# Pmaster-A9112-HOST_1.net
KiCad netlist of a schematic drawn in Altium Designer
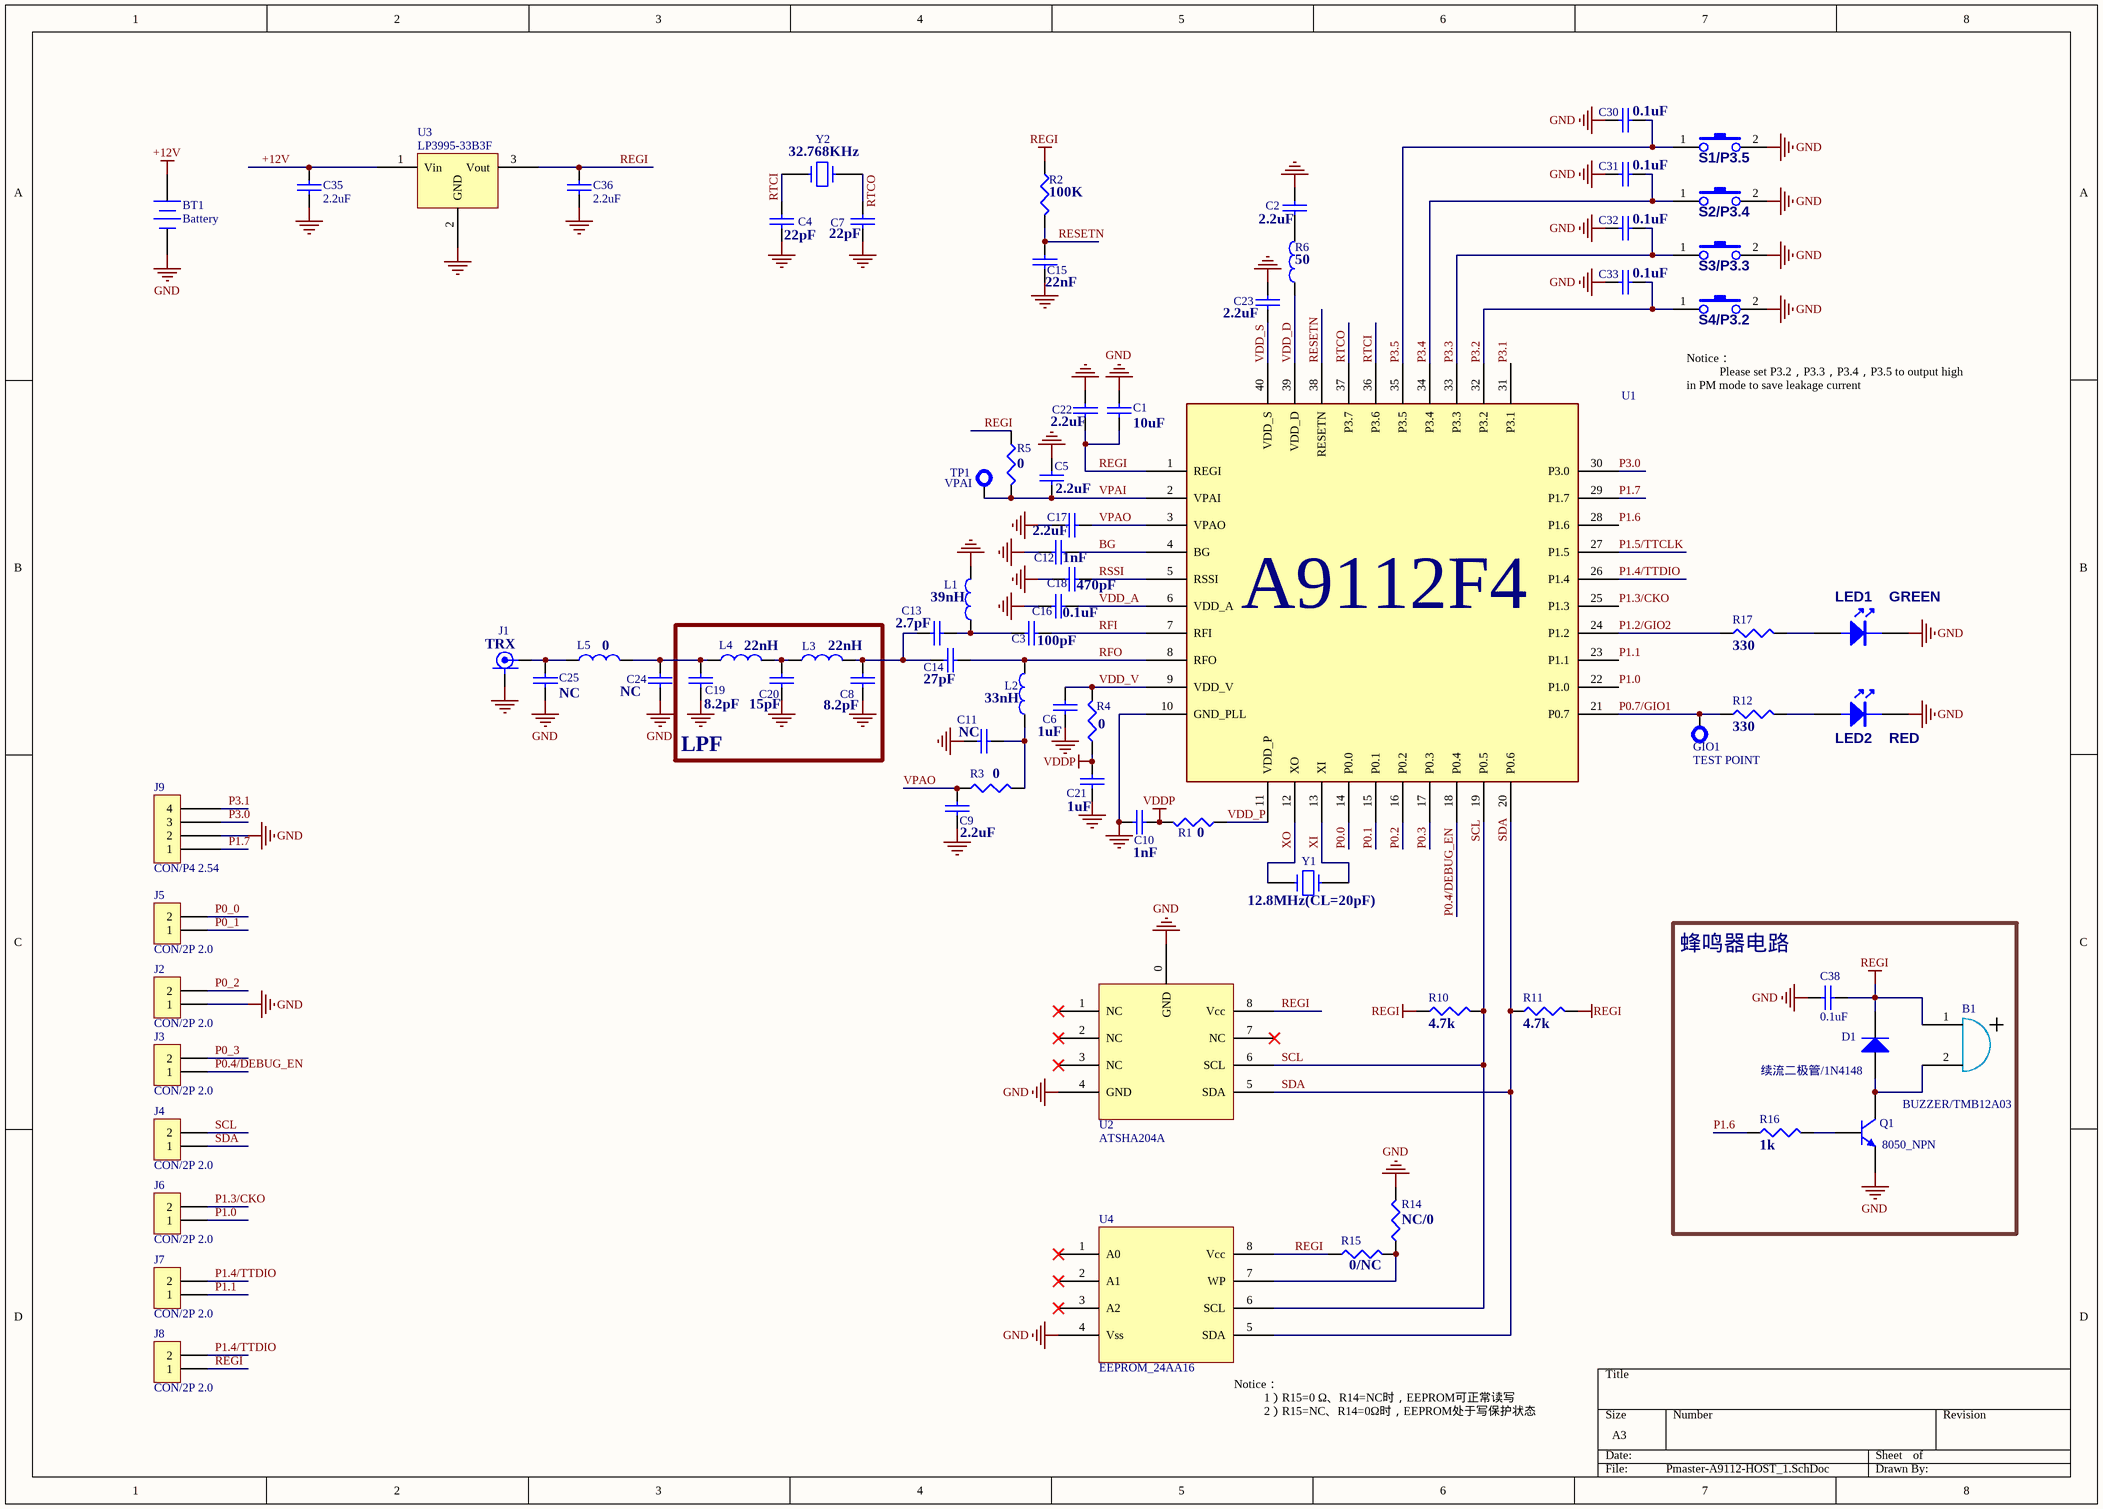
[diagram p0: Pmaster-A9112-HOST_1.SchDoc]

(export (version "E")
  (design (tool "Eeschema 10.0.6"))
  (components
    (comp (ref "B1")
      (value "BUZZER/TMB12A03")
      (footprint "BUZEER")
      (libsource (lib "my-amiccom") (part "BUZZER"))
    )
    (comp (ref "BT1")
      (value "Battery")
      (footprint "BAT-2")
      (description "Multicell Battery")
      (fields (field (name "PUBLISHER") "Altium Limited"))
      (libsource (lib "Miscellaneous Devices") (part "Battery"))
    )
    (comp (ref "C1") (value "10uF") (footprint "1206") (libsource (lib "*") (part "CAP")))
    (comp (ref "C2") (value "2.2uF") (footprint "0603") (libsource (lib "*") (part "CAP")))
    (comp (ref "C3") (value "100pF") (footprint "0402") (libsource (lib "*") (part "CAP")))
    (comp (ref "C4")
      (value "22pF")
      (footprint "0402")
      (description "Chip C")
      (libsource (lib "*") (part "C/0402"))
    )
    (comp (ref "C5") (value "2.2uF") (footprint "0603") (libsource (lib "*") (part "CAP")))
    (comp (ref "C6") (value "1uF") (footprint "0603") (libsource (lib "*") (part "CAP")))
    (comp (ref "C7")
      (value "22pF")
      (footprint "0402")
      (description "Chip C")
      (libsource (lib "*") (part "C/0402"))
    )
    (comp (ref "C8") (value "8.2pF") (footprint "0402") (libsource (lib "*") (part "CAP")))
    (comp (ref "C9")
      (value "2.2uF")
      (footprint "0603")
      (description "Chip C")
      (libsource (lib "*") (part "C/0603"))
    )
    (comp (ref "C10") (value "1nF") (footprint "0402") (libsource (lib "*") (part "CAP")))
    (comp (ref "C11")
      (value "NC")
      (footprint "0402")
      (description "Chip C")
      (libsource (lib "*") (part "C/0603"))
    )
    (comp (ref "C12") (value "1nF") (footprint "0402") (libsource (lib "*") (part "CAP")))
    (comp (ref "C13") (value "2.7pF") (footprint "0402") (libsource (lib "*") (part "CAP")))
    (comp (ref "C14") (value "27pF") (footprint "0402") (libsource (lib "*") (part "CAP")))
    (comp (ref "C15")
      (value "22nF")
      (footprint "0402")
      (description "Chip C")
      (libsource (lib "*") (part "C/1206"))
    )
    (comp (ref "C16") (value "0.1uF") (footprint "0603") (libsource (lib "*") (part "CAP")))
    (comp (ref "C17")
      (value "2.2uF")
      (footprint "0603")
      (description "Chip C")
      (libsource (lib "*") (part "C/0603"))
    )
    (comp (ref "C18") (value "470pF") (footprint "0402") (libsource (lib "*") (part "CAP")))
    (comp (ref "C19")
      (value "8.2pF")
      (footprint "0402")
      (description "Chip C")
      (libsource (lib "*") (part "C/0603"))
    )
    (comp (ref "C20")
      (value "15pF")
      (footprint "0402")
      (description "Chip C")
      (libsource (lib "*") (part "C/0603"))
    )
    (comp (ref "C21") (value "1uF") (footprint "0402") (libsource (lib "*") (part "CAP")))
    (comp (ref "C22") (value "2.2uF") (footprint "0603") (libsource (lib "*") (part "CAP")))
    (comp (ref "C23") (value "2.2uF") (footprint "0603") (libsource (lib "*") (part "CAP")))
    (comp (ref "C24") (value "NC") (footprint "0402") (libsource (lib "*") (part "CAP")))
    (comp (ref "C25") (value "NC") (footprint "0402") (libsource (lib "*") (part "CAP")))
    (comp (ref "C30") (value "0.1uF") (footprint "0603") (libsource (lib "*") (part "CAP")))
    (comp (ref "C31") (value "0.1uF") (footprint "0603") (libsource (lib "*") (part "CAP")))
    (comp (ref "C32") (value "0.1uF") (footprint "0603") (libsource (lib "*") (part "CAP")))
    (comp (ref "C33") (value "0.1uF") (footprint "0603") (libsource (lib "*") (part "CAP")))
    (comp (ref "C35") (value "2.2uF") (footprint "0603") (libsource (lib "") (part "CAP_1")))
    (comp (ref "C36")
      (value "2.2uF")
      (footprint "0603")
      (description "Chip C")
      (libsource (lib "*") (part "C/0603"))
    )
    (comp (ref "C38")
      (value "0.1uF")
      (footprint "A0402")
      (description "Chip C")
      (libsource (lib "*") (part "C/0603"))
    )
    (comp (ref "D1")
      (value "续流二极管/1N4148")
      (footprint "0805")
      (description "Default Diode")
      (fields (field (name "PUBLISHER") "Altium Limited"))
      (libsource (lib "Miscellaneous Devices") (part "Diode"))
    )
    (comp (ref "GIO1") (value "TEST POINT") (footprint "DIPOLE") (libsource (lib "my-amiccom") (part "TP")))
    (comp (ref "J1") (value "TRX") (footprint "SMA CONNECTOR") (libsource (lib "*") (part "SMA CONNECTOR")))
    (comp (ref "J2")
      (value "CON/2P 2.0")
      (footprint "HDR2_2.0")
      (description "Hole 36mil")
      (libsource (lib "my-amiccom") (part "CON/2P 2.0"))
    )
    (comp (ref "J3")
      (value "CON/2P 2.0")
      (footprint "HDR2_2.0")
      (description "Hole 36mil")
      (libsource (lib "my-amiccom") (part "CON/2P 2.0"))
    )
    (comp (ref "J4")
      (value "CON/2P 2.0")
      (footprint "HDR2_2.0")
      (description "Hole 36mil")
      (libsource (lib "my-amiccom") (part "CON/2P 2.0"))
    )
    (comp (ref "J5")
      (value "CON/2P 2.0")
      (footprint "HDR2_2.0")
      (description "Hole 36mil")
      (libsource (lib "my-amiccom") (part "CON/2P 2.0"))
    )
    (comp (ref "J6")
      (value "CON/2P 2.0")
      (footprint "HDR2_2.0")
      (description "Hole 36mil")
      (libsource (lib "my-amiccom") (part "CON/2P 2.0"))
    )
    (comp (ref "J7")
      (value "CON/2P 2.0")
      (footprint "HDR2_2.0")
      (description "Hole 36mil")
      (libsource (lib "my-amiccom") (part "CON/2P 2.0"))
    )
    (comp (ref "J8")
      (value "CON/2P 2.0")
      (footprint "HDR2_2.0")
      (description "Hole 36mil")
      (libsource (lib "my-amiccom") (part "CON/2P 2.0"))
    )
    (comp (ref "J9") (value "CON/P4 2.54") (libsource (lib "my-amiccom") (part "CON/P4 2.54")))
    (comp (ref "L1")
      (value "39nH")
      (footprint "0402")
      (description "Chip L")
      (libsource (lib "*") (part "L/0402"))
    )
    (comp (ref "L2")
      (value "33nH")
      (footprint "0402")
      (description "Chip L")
      (libsource (lib "*") (part "L/0402"))
    )
    (comp (ref "L3") (value "22nH") (footprint "0402") (libsource (lib "") (part "L/0603_1")))
    (comp (ref "L4") (value "22nH") (footprint "0402") (libsource (lib "") (part "L/0603_1")))
    (comp (ref "L5") (value "0") (footprint "0402") (libsource (lib "") (part "L/0603_1")))
    (comp (ref "LED1") (value "GREEN") (footprint "0603") (libsource (lib "my-amiccom") (part "LED")))
    (comp (ref "LED2") (value "RED") (footprint "0603") (libsource (lib "my-amiccom") (part "LED")))
    (comp (ref "Q1")
      (value "8050_NPN")
      (footprint "SOT-23_N")
      (description "NPN Bipolar Transistor")
      (fields (field (name "PUBLISHER") "Altium Limited"))
      (libsource (lib "Miscellaneous Devices") (part "NPN"))
    )
    (comp (ref "R1") (value "0") (footprint "0402") (libsource (lib "*") (part "RES1")))
    (comp (ref "R2")
      (value "100K")
      (footprint "0402")
      (description "Chip R")
      (libsource (lib "*") (part "R/0402"))
    )
    (comp (ref "R3")
      (value "0")
      (footprint "0402")
      (description "Chip  R")
      (libsource (lib "*") (part "R/0603"))
    )
    (comp (ref "R4")
      (value "0")
      (footprint "0402")
      (description "Chip  R")
      (libsource (lib "*") (part "R/0603"))
    )
    (comp (ref "R5") (value "0") (footprint "0402") (libsource (lib "*") (part "RES1")))
    (comp (ref "R6") (value "50") (footprint "0402") (libsource (lib "*") (part "L/0603")))
    (comp (ref "R10") (value "4.7k") (footprint "0402") (libsource (lib "*") (part "RES1")))
    (comp (ref "R11") (value "4.7k") (footprint "0402") (libsource (lib "*") (part "RES1")))
    (comp (ref "R12") (value "330") (footprint "0402") (libsource (lib "*") (part "RES1")))
    (comp (ref "R14") (value "NC/0") (footprint "0402") (libsource (lib "*") (part "RES1")))
    (comp (ref "R15") (value "0/NC") (footprint "0402") (libsource (lib "*") (part "RES1")))
    (comp (ref "R16") (value "1k") (footprint "0402") (libsource (lib "*") (part "RES1")))
    (comp (ref "R17") (value "330") (footprint "0402") (libsource (lib "*") (part "RES1")))
    (comp (ref "S1/P3.5")
      (value "SW-P~{B}2P")
      (footprint "SW2P")
      (libsource (lib "my-amiccom") (part "SW-PB{backslash}2P"))
    )
    (comp (ref "S2/P3.4")
      (value "SW-P~{B}2P")
      (footprint "SW2P")
      (libsource (lib "my-amiccom") (part "SW-PB{backslash}2P"))
    )
    (comp (ref "S3/P3.3")
      (value "SW-P~{B}2P")
      (footprint "SW2P")
      (libsource (lib "my-amiccom") (part "SW-PB{backslash}2P"))
    )
    (comp (ref "S4/P3.2")
      (value "SW-P~{B}2P")
      (footprint "SW2P")
      (libsource (lib "my-amiccom") (part "SW-PB{backslash}2P"))
    )
    (comp (ref "TP1") (value "VPAI") (footprint "HDR1_2.54") (libsource (lib "test LIB") (part "TP")))
    (comp (ref "U1")
      (value "A9112F4")
      (footprint "QFN 5*5 40L")
      (libsource (lib "AMICCOM-S") (part "A9112F4"))
    )
    (comp (ref "U2")
      (value "ATSHA204A")
      (footprint "UDFN_8P")
      (libsource (lib "my-amiccom") (part "ATSHA204A"))
    )
    (comp (ref "U3")
      (value "LP3995-33B3F")
      (footprint "SOT-223")
      (description "GMT 3.3V REGULTOR")
      (libsource (lib "*") (part "REG{backslash}G903{backslash}3.3V{backslash}SOT-223"))
    )
    (comp (ref "U4")
      (value "EEPROM_24AA16")
      (footprint "MSOP-MS8_N")
      (libsource (lib "my-amiccom") (part "EEPROM_24AA16"))
    )
    (comp (ref "Y1")
      (value "12.8MHz(CL=20pF)")
      (footprint "XTAL1")
      (description "Crystal")
      (libsource (lib "*") (part "CRYSTAL"))
    )
    (comp (ref "Y2")
      (value "32.768KHz")
      (footprint "xtal-3215")
      (description "Crystal")
      (libsource (lib "*") (part "CRYSTAL"))
    )
  )
  (nets
    (net (code "1") (name "+12V") (class "Default")
      (node (ref "BT1") (pin "1") (pinfunction "+_1") (pintype "passive"))
      (node (ref "C35") (pin "2") (pinfunction "2_2") (pintype "passive"))
      (node (ref "U3") (pin "1") (pinfunction "Vin_1") (pintype "passive"))
    )
    (net (code "2") (name "/BG") (class "Default")
      (node (ref "C12") (pin "1") (pinfunction "1_1") (pintype "passive"))
      (node (ref "U1") (pin "4") (pinfunction "BG_4") (pintype "passive"))
    )
    (net (code "3") (name "/P0.0") (class "Default")
      (node (ref "U1") (pin "14") (pinfunction "P0.0_14") (pintype "passive"))
    )
    (net (code "4") (name "/P0.1") (class "Default")
      (node (ref "U1") (pin "15") (pinfunction "P0.1_15") (pintype "passive"))
    )
    (net (code "5") (name "/P0.2") (class "Default")
      (node (ref "U1") (pin "16") (pinfunction "P0.2_16") (pintype "passive"))
    )
    (net (code "6") (name "/P0.3") (class "Default")
      (node (ref "U1") (pin "17") (pinfunction "P0.3_17") (pintype "passive"))
    )
    (net (code "7") (name "/P0.4{slash}DEBUG_EN") (class "Default")
      (node (ref "J3") (pin "1") (pinfunction "1_1") (pintype "passive"))
      (node (ref "U1") (pin "18") (pinfunction "P0.4_18") (pintype "passive"))
    )
    (net (code "8") (name "/P0.7{slash}GIO1") (class "Default")
      (node (ref "GIO1") (pin "1") (pinfunction "1_1") (pintype "passive"))
      (node (ref "R12") (pin "1") (pinfunction "1_1") (pintype "passive"))
      (node (ref "U1") (pin "21") (pinfunction "P0.7_21") (pintype "passive"))
    )
    (net (code "9") (name "/P0_0") (class "Default")
      (node (ref "J5") (pin "2") (pinfunction "2_2") (pintype "passive"))
    )
    (net (code "10") (name "/P0_1") (class "Default")
      (node (ref "J5") (pin "1") (pinfunction "1_1") (pintype "passive"))
    )
    (net (code "11") (name "/P0_2") (class "Default")
      (node (ref "J2") (pin "2") (pinfunction "2_2") (pintype "passive"))
    )
    (net (code "12") (name "/P0_3") (class "Default")
      (node (ref "J3") (pin "2") (pinfunction "2_2") (pintype "passive"))
    )
    (net (code "13") (name "/P1.0") (class "Default")
      (node (ref "J6") (pin "1") (pinfunction "1_1") (pintype "passive"))
      (node (ref "U1") (pin "22") (pinfunction "P1.0_22") (pintype "passive"))
    )
    (net (code "14") (name "/P1.1") (class "Default")
      (node (ref "J7") (pin "1") (pinfunction "1_1") (pintype "passive"))
      (node (ref "U1") (pin "23") (pinfunction "P1.1_23") (pintype "passive"))
    )
    (net (code "15") (name "/P1.2{slash}GIO2") (class "Default")
      (node (ref "R17") (pin "1") (pinfunction "1_1") (pintype "passive"))
      (node (ref "U1") (pin "24") (pinfunction "P1.2_24") (pintype "passive"))
    )
    (net (code "16") (name "/P1.3{slash}CKO") (class "Default")
      (node (ref "J6") (pin "2") (pinfunction "2_2") (pintype "passive"))
      (node (ref "U1") (pin "25") (pinfunction "P1.3_25") (pintype "passive"))
    )
    (net (code "17") (name "/P1.4{slash}TTDIO") (class "Default")
      (node (ref "J7") (pin "2") (pinfunction "2_2") (pintype "passive"))
      (node (ref "J8") (pin "2") (pinfunction "2_2") (pintype "passive"))
      (node (ref "U1") (pin "26") (pinfunction "P1.4_26") (pintype "passive"))
    )
    (net (code "18") (name "/P1.5{slash}TTCLK") (class "Default")
      (node (ref "U1") (pin "27") (pinfunction "P1.5_27") (pintype "passive"))
    )
    (net (code "19") (name "/P1.6") (class "Default")
      (node (ref "R16") (pin "1") (pinfunction "1_1") (pintype "passive"))
      (node (ref "U1") (pin "28") (pinfunction "P1.6_28") (pintype "passive"))
    )
    (net (code "20") (name "/P1.7") (class "Default")
      (node (ref "J9") (pin "1") (pinfunction "1_1") (pintype "power_in"))
      (node (ref "U1") (pin "29") (pinfunction "P1.7_29") (pintype "passive"))
    )
    (net (code "21") (name "/P3.0") (class "Default")
      (node (ref "J9") (pin "3") (pinfunction "3_3") (pintype "power_in"))
      (node (ref "U1") (pin "30") (pinfunction "P3.0_30") (pintype "passive"))
    )
    (net (code "22") (name "/P3.1") (class "Default")
      (node (ref "J9") (pin "4") (pinfunction "4_4") (pintype "power_in"))
      (node (ref "U1") (pin "31") (pinfunction "P3.1_31") (pintype "passive"))
    )
    (net (code "23") (name "/P3.2") (class "Default")
      (node (ref "C33") (pin "2") (pinfunction "2_2") (pintype "passive"))
      (node (ref "S4/P3.2") (pin "1") (pinfunction "1_1") (pintype "passive"))
      (node (ref "U1") (pin "32") (pinfunction "P3.2_32") (pintype "passive"))
    )
    (net (code "24") (name "/P3.3") (class "Default")
      (node (ref "C32") (pin "2") (pinfunction "2_2") (pintype "passive"))
      (node (ref "S3/P3.3") (pin "1") (pinfunction "1_1") (pintype "passive"))
      (node (ref "U1") (pin "33") (pinfunction "P3.3_33") (pintype "passive"))
    )
    (net (code "25") (name "/P3.4") (class "Default")
      (node (ref "C31") (pin "2") (pinfunction "2_2") (pintype "passive"))
      (node (ref "S2/P3.4") (pin "1") (pinfunction "1_1") (pintype "passive"))
      (node (ref "U1") (pin "34") (pinfunction "P3.4_34") (pintype "passive"))
    )
    (net (code "26") (name "/P3.5") (class "Default")
      (node (ref "C30") (pin "2") (pinfunction "2_2") (pintype "passive"))
      (node (ref "S1/P3.5") (pin "1") (pinfunction "1_1") (pintype "passive"))
      (node (ref "U1") (pin "35") (pinfunction "P3.5_35") (pintype "passive"))
    )
    (net (code "27") (name "/RESETN") (class "Default")
      (node (ref "C15") (pin "1") (pinfunction "1_1") (pintype "passive"))
      (node (ref "R2") (pin "2") (pinfunction "2_2") (pintype "passive"))
      (node (ref "U1") (pin "38") (pinfunction "RESETN_38") (pintype "passive"))
    )
    (net (code "28") (name "/RFI") (class "Default")
      (node (ref "C3") (pin "1") (pinfunction "1_1") (pintype "passive"))
      (node (ref "U1") (pin "7") (pinfunction "RFI_7") (pintype "passive"))
    )
    (net (code "29") (name "/RFO") (class "Default")
      (node (ref "C14") (pin "1") (pinfunction "1_1") (pintype "passive"))
      (node (ref "L2") (pin "2") (pinfunction "2_2") (pintype "passive"))
      (node (ref "U1") (pin "8") (pinfunction "RFO_8") (pintype "passive"))
    )
    (net (code "30") (name "/RSSI") (class "Default")
      (node (ref "C18") (pin "2") (pinfunction "2_2") (pintype "passive"))
      (node (ref "U1") (pin "5") (pinfunction "RSSI_5") (pintype "passive"))
    )
    (net (code "31") (name "/RTCI") (class "Default")
      (node (ref "C4") (pin "1") (pinfunction "1_1") (pintype "passive"))
      (node (ref "U1") (pin "36") (pinfunction "P3.6_36") (pintype "passive"))
      (node (ref "Y2") (pin "1") (pinfunction "1_1") (pintype "passive"))
    )
    (net (code "32") (name "/RTCO") (class "Default")
      (node (ref "C7") (pin "1") (pinfunction "1_1") (pintype "passive"))
      (node (ref "U1") (pin "37") (pinfunction "P3.7_37") (pintype "passive"))
      (node (ref "Y2") (pin "2") (pinfunction "2_2") (pintype "passive"))
    )
    (net (code "33") (name "/SCL") (class "Default")
      (node (ref "J4") (pin "2") (pinfunction "2_2") (pintype "passive"))
      (node (ref "R10") (pin "2") (pinfunction "2_2") (pintype "passive"))
      (node (ref "U1") (pin "19") (pinfunction "P0.5_19") (pintype "passive"))
      (node (ref "U2") (pin "6") (pinfunction "SCL_6") (pintype "passive"))
      (node (ref "U4") (pin "6") (pinfunction "SCL_6") (pintype "passive"))
    )
    (net (code "34") (name "/SDA") (class "Default")
      (node (ref "J4") (pin "1") (pinfunction "1_1") (pintype "passive"))
      (node (ref "R11") (pin "1") (pinfunction "1_1") (pintype "passive"))
      (node (ref "U1") (pin "20") (pinfunction "P0.6_20") (pintype "passive"))
      (node (ref "U2") (pin "5") (pinfunction "SDA_5") (pintype "passive"))
      (node (ref "U4") (pin "5") (pinfunction "SDA_5") (pintype "passive"))
    )
    (net (code "35") (name "/VDD_A") (class "Default")
      (node (ref "C16") (pin "2") (pinfunction "2_2") (pintype "passive"))
      (node (ref "U1") (pin "6") (pinfunction "VDD_A_6") (pintype "passive"))
    )
    (net (code "36") (name "/VDD_D") (class "Default")
      (node (ref "R6") (pin "1") (pinfunction "1_1") (pintype "passive"))
      (node (ref "U1") (pin "39") (pinfunction "VDD_D_39") (pintype "passive"))
    )
    (net (code "37") (name "/VDD_P") (class "Default")
      (node (ref "R1") (pin "1") (pinfunction "1_1") (pintype "passive"))
      (node (ref "U1") (pin "11") (pinfunction "VDD_P_11") (pintype "passive"))
    )
    (net (code "39") (name "/VDD_S") (class "Default")
      (node (ref "C23") (pin "2") (pinfunction "2_2") (pintype "passive"))
      (node (ref "U1") (pin "40") (pinfunction "VDD_S_40") (pintype "passive"))
    )
    (net (code "40") (name "/VDD_V") (class "Default")
      (node (ref "C6") (pin "1") (pinfunction "1_1") (pintype "passive"))
      (node (ref "R4") (pin "2") (pinfunction "2_2") (pintype "passive"))
      (node (ref "U1") (pin "9") (pinfunction "VDD_V_9") (pintype "passive"))
    )
    (net (code "41") (name "/VPAI") (class "Default")
      (node (ref "C5") (pin "1") (pinfunction "1_1") (pintype "passive"))
      (node (ref "R5") (pin "2") (pinfunction "2_2") (pintype "passive"))
      (node (ref "TP1") (pin "1") (pinfunction "1_1") (pintype "passive"))
      (node (ref "U1") (pin "2") (pinfunction "VPAI_2") (pintype "passive"))
    )
    (net (code "42") (name "/VPAO") (class "Default")
      (node (ref "C17") (pin "1") (pinfunction "1_1") (pintype "passive"))
      (node (ref "C9") (pin "1") (pinfunction "1_1") (pintype "passive"))
      (node (ref "R3") (pin "1") (pinfunction "1_1") (pintype "passive"))
      (node (ref "U1") (pin "3") (pinfunction "VPAO_3") (pintype "passive"))
    )
    (net (code "43") (name "/XI") (class "Default")
      (node (ref "U1") (pin "13") (pinfunction "XI_13") (pintype "passive"))
      (node (ref "Y1") (pin "1") (pinfunction "1_1") (pintype "passive"))
    )
    (net (code "44") (name "/XO") (class "Default")
      (node (ref "U1") (pin "12") (pinfunction "XO_12") (pintype "passive"))
      (node (ref "Y1") (pin "2") (pinfunction "2_2") (pintype "passive"))
    )
    (net (code "45") (name "GND") (class "Default")
      (node (ref "BT1") (pin "2") (pinfunction "-_2") (pintype "passive"))
      (node (ref "C1") (pin "2") (pinfunction "2_2") (pintype "passive"))
      (node (ref "C10") (pin "1") (pinfunction "1_1") (pintype "passive"))
      (node (ref "C11") (pin "1") (pinfunction "1_1") (pintype "passive"))
      (node (ref "C12") (pin "2") (pinfunction "2_2") (pintype "passive"))
      (node (ref "C15") (pin "2") (pinfunction "2_2") (pintype "passive"))
      (node (ref "C16") (pin "1") (pinfunction "1_1") (pintype "passive"))
      (node (ref "C17") (pin "2") (pinfunction "2_2") (pintype "passive"))
      (node (ref "C18") (pin "1") (pinfunction "1_1") (pintype "passive"))
      (node (ref "C19") (pin "2") (pinfunction "2_2") (pintype "passive"))
      (node (ref "C2") (pin "1") (pinfunction "1_1") (pintype "passive"))
      (node (ref "C20") (pin "2") (pinfunction "2_2") (pintype "passive"))
      (node (ref "C21") (pin "1") (pinfunction "1_1") (pintype "passive"))
      (node (ref "C22") (pin "1") (pinfunction "1_1") (pintype "passive"))
      (node (ref "C23") (pin "1") (pinfunction "1_1") (pintype "passive"))
      (node (ref "C24") (pin "1") (pinfunction "1_1") (pintype "passive"))
      (node (ref "C25") (pin "1") (pinfunction "1_1") (pintype "passive"))
      (node (ref "C30") (pin "1") (pinfunction "1_1") (pintype "passive"))
      (node (ref "C31") (pin "1") (pinfunction "1_1") (pintype "passive"))
      (node (ref "C32") (pin "1") (pinfunction "1_1") (pintype "passive"))
      (node (ref "C33") (pin "1") (pinfunction "1_1") (pintype "passive"))
      (node (ref "C35") (pin "1") (pinfunction "1_1") (pintype "passive"))
      (node (ref "C36") (pin "2") (pinfunction "2_2") (pintype "passive"))
      (node (ref "C38") (pin "1") (pinfunction "1_1") (pintype "passive"))
      (node (ref "C4") (pin "2") (pinfunction "2_2") (pintype "passive"))
      (node (ref "C5") (pin "2") (pinfunction "2_2") (pintype "passive"))
      (node (ref "C7") (pin "2") (pinfunction "2_2") (pintype "passive"))
      (node (ref "C8") (pin "1") (pinfunction "1_1") (pintype "passive"))
      (node (ref "C9") (pin "2") (pinfunction "2_2") (pintype "passive"))
      (node (ref "J1") (pin "0") (pinfunction "SHIELD_0") (pintype "passive"))
      (node (ref "J2") (pin "1") (pinfunction "1_1") (pintype "passive"))
      (node (ref "J9") (pin "2") (pinfunction "2_2") (pintype "power_in"))
      (node (ref "L1") (pin "2") (pinfunction "2_2") (pintype "passive"))
      (node (ref "LED1") (pin "2") (pinfunction "K_2") (pintype "passive"))
      (node (ref "LED2") (pin "2") (pinfunction "K_2") (pintype "passive"))
      (node (ref "Q1") (pin "3") (pinfunction "E_3") (pintype "passive"))
      (node (ref "R14") (pin "2") (pinfunction "2_2") (pintype "passive"))
      (node (ref "S1/P3.5") (pin "2") (pinfunction "2_2") (pintype "passive"))
      (node (ref "S2/P3.4") (pin "2") (pinfunction "2_2") (pintype "passive"))
      (node (ref "S3/P3.3") (pin "2") (pinfunction "2_2") (pintype "passive"))
      (node (ref "S4/P3.2") (pin "2") (pinfunction "2_2") (pintype "passive"))
      (node (ref "U1") (pin "10") (pinfunction "GND_PLL_10") (pintype "passive"))
      (node (ref "U2") (pin "0") (pinfunction "GND_0") (pintype "passive"))
      (node (ref "U2") (pin "4") (pinfunction "GND_4") (pintype "passive"))
      (node (ref "U3") (pin "2") (pinfunction "GND_2") (pintype "passive"))
      (node (ref "U4") (pin "4") (pinfunction "Vss_4") (pintype "passive"))
    )
    (net (code "46") (name "Net-(C2-Pad2)") (class "Default")
      (node (ref "C2") (pin "2") (pinfunction "2_2") (pintype "passive"))
      (node (ref "R6") (pin "2") (pinfunction "2_2") (pintype "passive"))
    )
    (net (code "47") (name "Net-(C11-Pad2)") (class "Default")
      (node (ref "C11") (pin "2") (pinfunction "2_2") (pintype "passive"))
      (node (ref "L2") (pin "1") (pinfunction "1_1") (pintype "passive"))
      (node (ref "R3") (pin "2") (pinfunction "2_2") (pintype "passive"))
    )
    (net (code "48") (name "Net-(C13-Pad1)") (class "Default")
      (node (ref "C13") (pin "1") (pinfunction "1_1") (pintype "passive"))
      (node (ref "C3") (pin "2") (pinfunction "2_2") (pintype "passive"))
      (node (ref "L1") (pin "1") (pinfunction "1_1") (pintype "passive"))
    )
    (net (code "49") (name "Net-(C13-Pad2)") (class "Default")
      (node (ref "C13") (pin "2") (pinfunction "2_2") (pintype "passive"))
      (node (ref "C14") (pin "2") (pinfunction "2_2") (pintype "passive"))
      (node (ref "C8") (pin "2") (pinfunction "2_2") (pintype "passive"))
      (node (ref "L3") (pin "2") (pinfunction "2_2") (pintype "passive"))
    )
    (net (code "50") (name "Net-(C19-Pad1)") (class "Default")
      (node (ref "C19") (pin "1") (pinfunction "1_1") (pintype "passive"))
      (node (ref "C24") (pin "2") (pinfunction "2_2") (pintype "passive"))
      (node (ref "L4") (pin "1") (pinfunction "1_1") (pintype "passive"))
      (node (ref "L5") (pin "2") (pinfunction "2_2") (pintype "passive"))
    )
    (net (code "51") (name "Net-(C20-Pad1)") (class "Default")
      (node (ref "C20") (pin "1") (pinfunction "1_1") (pintype "passive"))
      (node (ref "L3") (pin "1") (pinfunction "1_1") (pintype "passive"))
      (node (ref "L4") (pin "2") (pinfunction "2_2") (pintype "passive"))
    )
    (net (code "52") (name "Net-(D1-A)") (class "Default")
      (node (ref "B1") (pin "2") (pintype "passive"))
      (node (ref "D1") (pin "1") (pinfunction "A_1") (pintype "passive"))
      (node (ref "Q1") (pin "1") (pinfunction "C_1") (pintype "passive"))
    )
    (net (code "53") (name "Net-(J1-CENTER_1)") (class "Default")
      (node (ref "C25") (pin "2") (pinfunction "2_2") (pintype "passive"))
      (node (ref "J1") (pin "1") (pinfunction "CENTER_1_1") (pintype "passive"))
      (node (ref "L5") (pin "1") (pinfunction "1_1") (pintype "passive"))
    )
    (net (code "54") (name "Net-(LED1-A)") (class "Default")
      (node (ref "LED1") (pin "1") (pinfunction "A_1") (pintype "passive"))
      (node (ref "R17") (pin "2") (pinfunction "2_2") (pintype "passive"))
    )
    (net (code "55") (name "Net-(LED2-A)") (class "Default")
      (node (ref "LED2") (pin "1") (pinfunction "A_1") (pintype "passive"))
      (node (ref "R12") (pin "2") (pinfunction "2_2") (pintype "passive"))
    )
    (net (code "56") (name "Net-(Q1-B)") (class "Default")
      (node (ref "Q1") (pin "2") (pinfunction "B_2") (pintype "passive"))
      (node (ref "R16") (pin "2") (pinfunction "2_2") (pintype "passive"))
    )
    (net (code "57") (name "Net-(U4-WP)") (class "Default")
      (node (ref "R14") (pin "1") (pinfunction "1_1") (pintype "passive"))
      (node (ref "R15") (pin "2") (pinfunction "2_2") (pintype "passive"))
      (node (ref "U4") (pin "7") (pinfunction "WP_7") (pintype "passive"))
    )
    (net (code "58") (name "REGI") (class "Default")
      (node (ref "B1") (pin "1") (pintype "passive"))
      (node (ref "C1") (pin "1") (pinfunction "1_1") (pintype "passive"))
      (node (ref "C22") (pin "2") (pinfunction "2_2") (pintype "passive"))
      (node (ref "C36") (pin "1") (pinfunction "1_1") (pintype "passive"))
      (node (ref "C38") (pin "2") (pinfunction "2_2") (pintype "passive"))
      (node (ref "D1") (pin "2") (pinfunction "K_2") (pintype "passive"))
      (node (ref "J8") (pin "1") (pinfunction "1_1") (pintype "passive"))
      (node (ref "R10") (pin "1") (pinfunction "1_1") (pintype "passive"))
      (node (ref "R11") (pin "2") (pinfunction "2_2") (pintype "passive"))
      (node (ref "R15") (pin "1") (pinfunction "1_1") (pintype "passive"))
      (node (ref "R2") (pin "1") (pinfunction "1_1") (pintype "passive"))
      (node (ref "R5") (pin "1") (pinfunction "1_1") (pintype "passive"))
      (node (ref "U1") (pin "1") (pinfunction "REGI_1") (pintype "passive"))
      (node (ref "U2") (pin "8") (pinfunction "Vcc_8") (pintype "passive"))
      (node (ref "U3") (pin "3") (pinfunction "Vout_3") (pintype "passive"))
      (node (ref "U4") (pin "8") (pinfunction "Vcc_8") (pintype "passive"))
    )
    (net (code "59") (name "VCO_GND") (class "Default")
      (node (ref "C6") (pin "2") (pinfunction "2_2") (pintype "passive"))
    )
    (net (code "60") (name "VDDP") (class "Default")
      (node (ref "C10") (pin "2") (pinfunction "2_2") (pintype "passive"))
      (node (ref "C21") (pin "2") (pinfunction "2_2") (pintype "passive"))
      (node (ref "R1") (pin "2") (pinfunction "2_2") (pintype "passive"))
      (node (ref "R4") (pin "1") (pinfunction "1_1") (pintype "passive"))
    )
    (net (code "61") (name "unconnected-(U2-NC-Pad1)") (class "Default")
      (node (ref "U2") (pin "1") (pinfunction "NC_1") (pintype "passive+no_connect"))
    )
    (net (code "62") (name "unconnected-(U2-NC-Pad2)") (class "Default")
      (node (ref "U2") (pin "2") (pinfunction "NC_2") (pintype "passive+no_connect"))
    )
    (net (code "63") (name "unconnected-(U2-NC-Pad3)") (class "Default")
      (node (ref "U2") (pin "3") (pinfunction "NC_3") (pintype "passive+no_connect"))
    )
    (net (code "64") (name "unconnected-(U2-NC-Pad7)") (class "Default")
      (node (ref "U2") (pin "7") (pinfunction "NC_7") (pintype "passive+no_connect"))
    )
    (net (code "65") (name "unconnected-(U4-A0-Pad1)") (class "Default")
      (node (ref "U4") (pin "1") (pinfunction "A0_1") (pintype "passive+no_connect"))
    )
    (net (code "66") (name "unconnected-(U4-A1-Pad2)") (class "Default")
      (node (ref "U4") (pin "2") (pinfunction "A1_2") (pintype "passive+no_connect"))
    )
    (net (code "67") (name "unconnected-(U4-A2-Pad3)") (class "Default")
      (node (ref "U4") (pin "3") (pinfunction "A2_3") (pintype "passive+no_connect"))
    )
  )
)
